# MCU.net
KiCad netlist of a schematic drawn in Altium Designer
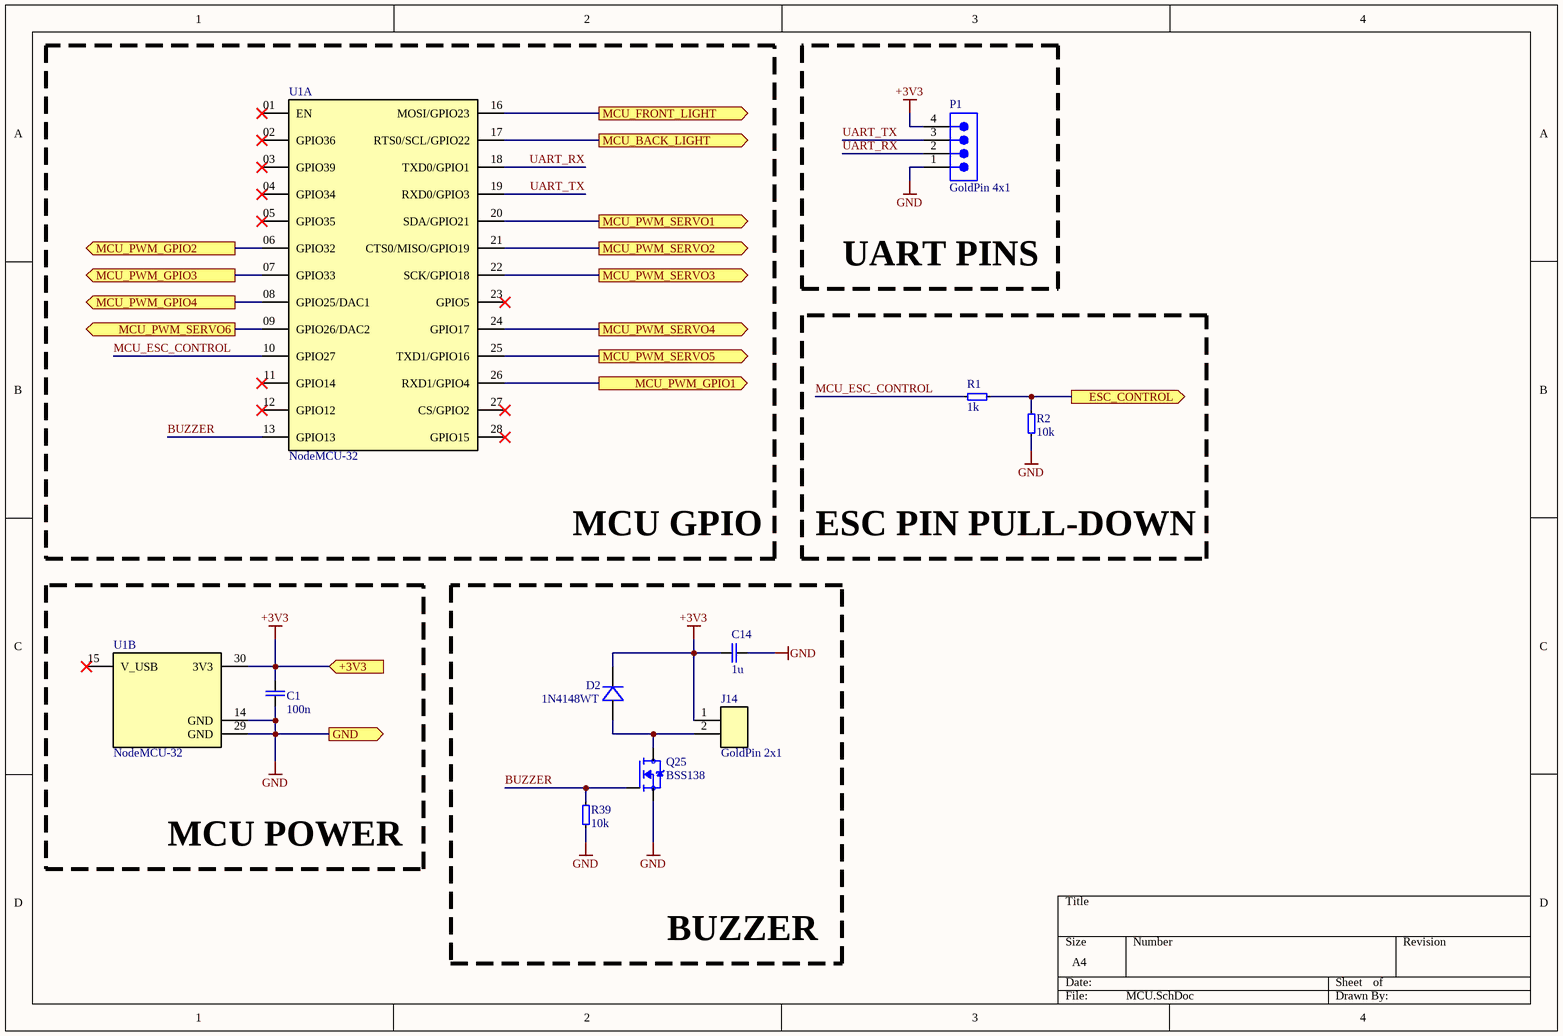
[diagram p0: MCU.SchDoc]

(export (version "E")
  (design (tool "Eeschema 10.0.6"))
  (components
    (comp (ref "C1")
      (value "100n")
      (footprint "C0402")
      (description "Generic SMD 0402 Ceramic Capacitor")
      (libsource (lib "PolSl Racing - Electrical") (part "Capacitor"))
    )
    (comp (ref "C14")
      (value "1u")
      (footprint "C0603")
      (description "Generic 0603 SMD Ceramic Capacitor")
      (libsource (lib "PolSl Racing - Electrical") (part "Capacitor"))
    )
    (comp (ref "D2")
      (value "1N4148WT")
      (footprint "SMBJSeries_LTF")
      (description "Description")
      (fields
        (field (name "MANUFACTURER_PART_NUMBER") "SMBJ7.0A")
        (field (name "COPYRIGHT") "Copyright (C) 2025 Ultra Librarian. All rights reserved.")
      )
      (libsource (lib "Tractor2000") (part "1N4148WT"))
    )
    (comp (ref "J14")
      (value "GoldPin 2x1")
      (footprint "HARWIN_M20-9990246")
      (description "2.54mm (0.1) Pitch SIL Vertical Throughboard Pin Header, 6.1mm mating pin height, tin, 2 contacts")
      (fields (field (name "MF") "Harwin") (field (name "MP") "M20-9990246"))
      (libsource (lib "Tractor2000") (part "GoldPin 2x1"))
    )
    (comp (ref "P1")
      (value "GoldPin 4x1")
      (footprint "SMTC-TSW-104-08-X-S")
      (description "TSW - Samtec 2.54mm Pin Header 13.46mm Overall Pin Length 5.08mm Tail (08) (mcv)(TO22)")
      (fields (field (name "MANUFACTURER") "Molex"))
      (libsource (lib "PolSl Racing - Electrical") (part "GoldPin 4x1"))
    )
    (comp (ref "Q25")
      (value "BSS138")
      (footprint "SOT95P240X111-3N")
      (description "N-Channel 50 V 220mA (Ta) 350mW (Ta) Surface Mount SOT-23-3")
      (fields (field (name "MF") "onsemi"))
      (libsource (lib "Tractor2000") (part "BSS138"))
    )
    (comp (ref "R1")
      (value "1k")
      (footprint "R0402")
      (description "Generic 0402 SMD Resistor")
      (libsource (lib "PolSl Racing - Electrical") (part "Resistor"))
    )
    (comp (ref "R2")
      (value "10k")
      (footprint "R0402")
      (description "Generic 0402 SMD Resistor")
      (libsource (lib "PolSl Racing - Electrical") (part "Resistor"))
    )
    (comp (ref "R39")
      (value "10k")
      (footprint "R0603")
      (description "Generic 0603 SMD Resistor")
      (libsource (lib "PolSl Racing - Electrical") (part "Resistor"))
    )
    (comp (ref "U1")
      (value "NodeMCU-32")
      (footprint "NodeMCU-32")
      (fields (field (name "MF") "Samtec Inc.") (field (name "MP") "TS-115-T-A"))
      (libsource (lib "Tractor2000") (part "NodeMCU-32"))
    )
  )
  (nets
    (net (code "1") (name "+3V3") (class "Default")
      (node (ref "C1") (pin "2") (pinfunction "2_2") (pintype "passive"))
      (node (ref "C14") (pin "2") (pinfunction "2_2") (pintype "passive"))
      (node (ref "D2") (pin "1") (pinfunction "1_1") (pintype "passive"))
      (node (ref "J14") (pin "1") (pinfunction "1_1") (pintype "passive"))
      (node (ref "P1") (pin "4") (pinfunction "4_4") (pintype "passive"))
      (node (ref "U1") (pin "30") (pinfunction "3V3_30") (pintype "passive"))
    )
    (net (code "2") (name "/BUZZER") (class "Default")
      (node (ref "Q25") (pin "1") (pinfunction "G_1") (pintype "passive"))
      (node (ref "R39") (pin "2") (pinfunction "2_2") (pintype "passive"))
      (node (ref "U1") (pin "13") (pinfunction "GPIO13_13") (pintype "passive"))
    )
    (net (code "3") (name "/ESC_CONTROL") (class "Default")
      (node (ref "R1") (pin "2") (pinfunction "2_2") (pintype "passive"))
      (node (ref "R2") (pin "2") (pinfunction "2_2") (pintype "passive"))
    )
    (net (code "4") (name "/MCU_BACK_LIGHT") (class "Default")
      (node (ref "U1") (pin "17") (pinfunction "RTS0/SCL/GPIO22_17") (pintype "passive"))
    )
    (net (code "5") (name "/MCU_ESC_CONTROL") (class "Default")
      (node (ref "R1") (pin "1") (pinfunction "1_1") (pintype "passive"))
      (node (ref "U1") (pin "10") (pinfunction "GPIO27_10") (pintype "passive"))
    )
    (net (code "6") (name "/MCU_FRONT_LIGHT") (class "Default")
      (node (ref "U1") (pin "16") (pinfunction "MOSI/GPIO23_16") (pintype "passive"))
    )
    (net (code "7") (name "/MCU_PWM_GPIO1") (class "Default")
      (node (ref "U1") (pin "26") (pinfunction "RXD1/GPIO4_26") (pintype "passive"))
    )
    (net (code "8") (name "/MCU_PWM_GPIO2") (class "Default")
      (node (ref "U1") (pin "06") (pinfunction "GPIO32_06") (pintype "passive"))
    )
    (net (code "9") (name "/MCU_PWM_GPIO3") (class "Default")
      (node (ref "U1") (pin "07") (pinfunction "GPIO33_07") (pintype "passive"))
    )
    (net (code "10") (name "/MCU_PWM_GPIO4") (class "Default")
      (node (ref "U1") (pin "08") (pinfunction "GPIO25/DAC1_08") (pintype "passive"))
    )
    (net (code "11") (name "/MCU_PWM_SERVO1") (class "Default")
      (node (ref "U1") (pin "20") (pinfunction "SDA/GPIO21_20") (pintype "passive"))
    )
    (net (code "12") (name "/MCU_PWM_SERVO2") (class "Default")
      (node (ref "U1") (pin "21") (pinfunction "CTS0/MISO/GPIO19_21") (pintype "passive"))
    )
    (net (code "13") (name "/MCU_PWM_SERVO3") (class "Default")
      (node (ref "U1") (pin "22") (pinfunction "SCK/GPIO18_22") (pintype "passive"))
    )
    (net (code "14") (name "/MCU_PWM_SERVO4") (class "Default")
      (node (ref "U1") (pin "24") (pinfunction "GPIO17_24") (pintype "passive"))
    )
    (net (code "15") (name "/MCU_PWM_SERVO5") (class "Default")
      (node (ref "U1") (pin "25") (pinfunction "TXD1/GPIO16_25") (pintype "passive"))
    )
    (net (code "16") (name "/MCU_PWM_SERVO6") (class "Default")
      (node (ref "U1") (pin "09") (pinfunction "GPIO26/DAC2_09") (pintype "passive"))
    )
    (net (code "17") (name "/UART_RX") (class "Default")
      (node (ref "P1") (pin "2") (pinfunction "2_2") (pintype "passive"))
      (node (ref "U1") (pin "18") (pinfunction "TXD0/GPIO1_18") (pintype "passive"))
    )
    (net (code "18") (name "/UART_TX") (class "Default")
      (node (ref "P1") (pin "3") (pinfunction "3_3") (pintype "passive"))
      (node (ref "U1") (pin "19") (pinfunction "RXD0/GPIO3_19") (pintype "passive"))
    )
    (net (code "19") (name "GND") (class "Default")
      (node (ref "C1") (pin "1") (pinfunction "1_1") (pintype "passive"))
      (node (ref "C14") (pin "1") (pinfunction "1_1") (pintype "passive"))
      (node (ref "P1") (pin "1") (pinfunction "1_1") (pintype "passive"))
      (node (ref "Q25") (pin "2") (pinfunction "S_2") (pintype "passive"))
      (node (ref "R2") (pin "1") (pinfunction "1_1") (pintype "passive"))
      (node (ref "R39") (pin "1") (pinfunction "1_1") (pintype "passive"))
      (node (ref "U1") (pin "14") (pinfunction "GND_14") (pintype "passive"))
      (node (ref "U1") (pin "29") (pinfunction "GND_29") (pintype "passive"))
    )
    (net (code "20") (name "Net-(Q25-D)") (class "Default")
      (node (ref "D2") (pin "2") (pinfunction "2_2") (pintype "passive"))
      (node (ref "J14") (pin "2") (pinfunction "2_2") (pintype "passive"))
      (node (ref "Q25") (pin "3") (pinfunction "D_3") (pintype "passive"))
    )
    (net (code "21") (name "unconnected-(U1A-CS{slash}GPIO2-Pad27)") (class "Default")
      (node (ref "U1") (pin "27") (pinfunction "CS/GPIO2_27") (pintype "passive+no_connect"))
    )
    (net (code "22") (name "unconnected-(U1A-EN-Pad01)") (class "Default")
      (node (ref "U1") (pin "01") (pinfunction "EN_01") (pintype "passive+no_connect"))
    )
    (net (code "23") (name "unconnected-(U1A-GPIO5-Pad23)") (class "Default")
      (node (ref "U1") (pin "23") (pinfunction "GPIO5_23") (pintype "passive+no_connect"))
    )
    (net (code "24") (name "unconnected-(U1A-GPIO12-Pad12)") (class "Default")
      (node (ref "U1") (pin "12") (pinfunction "GPIO12_12") (pintype "passive+no_connect"))
    )
    (net (code "25") (name "unconnected-(U1A-GPIO14-Pad11)") (class "Default")
      (node (ref "U1") (pin "11") (pinfunction "GPIO14_11") (pintype "passive+no_connect"))
    )
    (net (code "26") (name "unconnected-(U1A-GPIO15-Pad28)") (class "Default")
      (node (ref "U1") (pin "28") (pinfunction "GPIO15_28") (pintype "passive+no_connect"))
    )
    (net (code "27") (name "unconnected-(U1A-GPIO34-Pad04)") (class "Default")
      (node (ref "U1") (pin "04") (pinfunction "GPIO34_04") (pintype "passive+no_connect"))
    )
    (net (code "28") (name "unconnected-(U1A-GPIO35-Pad05)") (class "Default")
      (node (ref "U1") (pin "05") (pinfunction "GPIO35_05") (pintype "passive+no_connect"))
    )
    (net (code "29") (name "unconnected-(U1A-GPIO36-Pad02)") (class "Default")
      (node (ref "U1") (pin "02") (pinfunction "GPIO36_02") (pintype "passive+no_connect"))
    )
    (net (code "30") (name "unconnected-(U1A-GPIO39-Pad03)") (class "Default")
      (node (ref "U1") (pin "03") (pinfunction "GPIO39_03") (pintype "passive+no_connect"))
    )
    (net (code "31") (name "unconnected-(U1B-V_USB-Pad15)") (class "Default")
      (node (ref "U1") (pin "15") (pinfunction "V_USB_15") (pintype "passive+no_connect"))
    )
  )
)
